# board.net
KiCad netlist of a schematic drawn in EAGLE
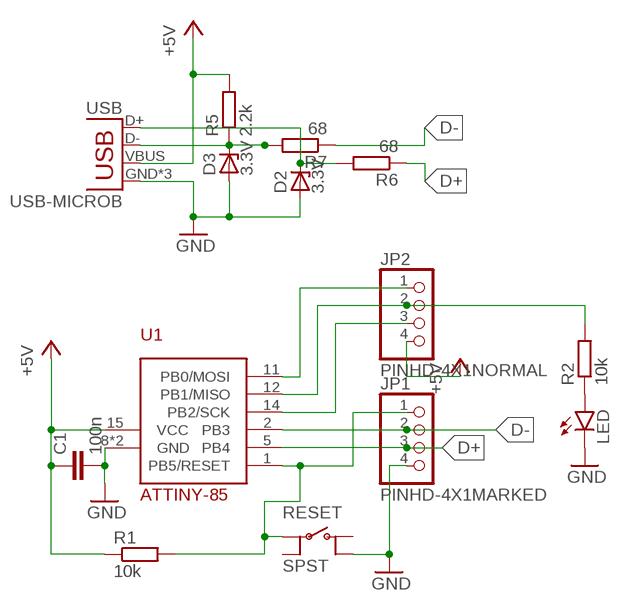
[diagram p0: schematic, sheet 1]

(export (version "E")
  (design (tool "Eeschema 10.0.6"))
  (components
    (comp (ref "C1")
      (value "100n")
      (footprint "eagle-import:C0603")
      (libsource (lib "eagle-import") (part "C-EUC0603"))
    )
    (comp (ref "D2")
      (value "3.3V")
      (footprint "eagle-import:SOD80C")
      (libsource (lib "eagle-import") (part "ZENER-DIODESOD80C"))
    )
    (comp (ref "D3")
      (value "3.3V")
      (footprint "eagle-import:SOD80C")
      (libsource (lib "eagle-import") (part "ZENER-DIODESOD80C"))
    )
    (comp (ref "JP1")
      (value "PINHD-4X1MARKED")
      (footprint "eagle-import:PINHD-1X4-MARKED")
      (libsource (lib "eagle-import") (part "PINHD-4X1MARKED"))
    )
    (comp (ref "JP2")
      (value "PINHD-4X1NORMAL")
      (footprint "eagle-import:PINHD-1X4")
      (libsource (lib "eagle-import") (part "PINHD-4X1NORMAL"))
    )
    (comp (ref "LED")
      (value "LED0603")
      (footprint "eagle-import:LED-0603")
      (libsource (lib "eagle-import") (part "LED0603"))
    )
    (comp (ref "R1")
      (value "10k")
      (footprint "eagle-import:R0402")
      (libsource (lib "eagle-import") (part "R-EU_R0402"))
    )
    (comp (ref "R2")
      (value "10k")
      (footprint "eagle-import:R0402")
      (libsource (lib "eagle-import") (part "R-EU_R0402"))
    )
    (comp (ref "R5")
      (value "2.2k")
      (footprint "eagle-import:R0402")
      (libsource (lib "eagle-import") (part "R-EU_R0402"))
    )
    (comp (ref "R6")
      (value "68")
      (footprint "eagle-import:R0402")
      (libsource (lib "eagle-import") (part "R-EU_R0402"))
    )
    (comp (ref "R7")
      (value "68")
      (footprint "eagle-import:R0402")
      (libsource (lib "eagle-import") (part "R-EU_R0402"))
    )
    (comp (ref "RESET")
      (value "SPST")
      (footprint "eagle-import:WUERTH-SPST-SMD")
      (libsource (lib "eagle-import") (part "SPST"))
    )
    (comp (ref "U1")
      (value "ATTINY-85")
      (footprint "eagle-import:QFN20")
      (libsource (lib "eagle-import") (part "ATTINY-85QFN-EARTHED-CENTER"))
    )
    (comp (ref "USB")
      (value "USB-MICROB")
      (footprint "eagle-import:USB-MICROB")
      (libsource (lib "eagle-import") (part "USB-MICROB"))
    )
  )
  (nets
    (net (code "1") (name "+5V") (class "Default")
      (node (ref "C1") (pin "1") (pinfunction "1_1") (pintype "passive"))
      (node (ref "JP2") (pin "4") (pinfunction "4_4") (pintype "passive"))
      (node (ref "R1") (pin "1") (pinfunction "1_1") (pintype "passive"))
      (node (ref "R5") (pin "2") (pinfunction "2_2") (pintype "passive"))
      (node (ref "U1") (pin "15") (pinfunction "VCC_15") (pintype "power_in"))
      (node (ref "USB") (pin "VBUS") (pinfunction "VBUS_VBUS") (pintype "bidirectional"))
    )
    (net (code "2") (name "D+") (class "Default")
      (node (ref "JP1") (pin "3") (pinfunction "3_3") (pintype "passive"))
      (node (ref "R6") (pin "1") (pinfunction "1_1") (pintype "passive"))
      (node (ref "U1") (pin "5") (pinfunction "PB4_5") (pintype "bidirectional"))
    )
    (net (code "3") (name "D-") (class "Default")
      (node (ref "JP1") (pin "2") (pinfunction "2_2") (pintype "passive"))
      (node (ref "R7") (pin "1") (pinfunction "1_1") (pintype "passive"))
      (node (ref "U1") (pin "2") (pinfunction "PB3_2") (pintype "bidirectional"))
    )
    (net (code "4") (name "GND") (class "Default")
      (node (ref "C1") (pin "2") (pinfunction "2_2") (pintype "passive"))
      (node (ref "D2") (pin "A") (pinfunction "A_A") (pintype "passive"))
      (node (ref "D3") (pin "A") (pinfunction "A_A") (pintype "passive"))
      (node (ref "JP1") (pin "4") (pinfunction "4_4") (pintype "passive"))
      (node (ref "LED") (pin "C") (pinfunction "C_C") (pintype "passive"))
      (node (ref "RESET") (pin "4") (pinfunction "O2_4") (pintype "passive"))
      (node (ref "U1") (pin "8") (pinfunction "GND_8") (pintype "power_in"))
      (node (ref "U1") (pin "EP") (pinfunction "GND_EP") (pintype "power_in"))
      (node (ref "USB") (pin "GND") (pinfunction "GND_GND") (pintype "bidirectional"))
      (node (ref "USB") (pin "MT1") (pinfunction "GND_MT1") (pintype "bidirectional"))
      (node (ref "USB") (pin "MT2") (pinfunction "GND_MT2") (pintype "bidirectional"))
    )
    (net (code "5") (name "Net-(D2-PadC)") (class "Default")
      (node (ref "D2") (pin "C") (pinfunction "C_C") (pintype "passive"))
      (node (ref "R6") (pin "2") (pinfunction "2_2") (pintype "passive"))
      (node (ref "USB") (pin "D+") (pinfunction "D+_D+") (pintype "bidirectional"))
    )
    (net (code "6") (name "Net-(D3-PadC)") (class "Default")
      (node (ref "D3") (pin "C") (pinfunction "C_C") (pintype "passive"))
      (node (ref "R5") (pin "1") (pinfunction "1_1") (pintype "passive"))
      (node (ref "R7") (pin "2") (pinfunction "2_2") (pintype "passive"))
      (node (ref "USB") (pin "D-") (pinfunction "D-_D-") (pintype "bidirectional"))
    )
    (net (code "7") (name "Net-(LED-PadA)") (class "Default")
      (node (ref "LED") (pin "A") (pinfunction "A_A") (pintype "passive"))
      (node (ref "R2") (pin "1") (pinfunction "1_1") (pintype "passive"))
    )
    (net (code "8") (name "Net-(RESET-P)") (class "Default")
      (node (ref "JP1") (pin "1") (pinfunction "1_1") (pintype "passive"))
      (node (ref "R1") (pin "2") (pinfunction "2_2") (pintype "passive"))
      (node (ref "RESET") (pin "1") (pinfunction "P_1") (pintype "passive"))
      (node (ref "U1") (pin "1") (pinfunction "PB5/RESET_1") (pintype "bidirectional"))
    )
    (net (code "9") (name "Net-(U1-PB0{slash}MOSI)") (class "Default")
      (node (ref "JP2") (pin "1") (pinfunction "1_1") (pintype "passive"))
      (node (ref "U1") (pin "11") (pinfunction "PB0/MOSI_11") (pintype "bidirectional"))
    )
    (net (code "10") (name "Net-(U1-PB1{slash}MISO)") (class "Default")
      (node (ref "JP2") (pin "2") (pinfunction "2_2") (pintype "passive"))
      (node (ref "R2") (pin "2") (pinfunction "2_2") (pintype "passive"))
      (node (ref "U1") (pin "12") (pinfunction "PB1/MISO_12") (pintype "bidirectional"))
    )
    (net (code "11") (name "Net-(U1-PB2{slash}SCK)") (class "Default")
      (node (ref "JP2") (pin "3") (pinfunction "3_3") (pintype "passive"))
      (node (ref "U1") (pin "14") (pinfunction "PB2/SCK_14") (pintype "bidirectional"))
    )
    (net (code "12") (name "unconnected-(RESET-O-Pad2)") (class "Default")
      (node (ref "RESET") (pin "2") (pinfunction "O_2") (pintype "passive"))
    )
    (net (code "13") (name "unconnected-(RESET-P2-Pad3)") (class "Default")
      (node (ref "RESET") (pin "3") (pinfunction "P2_3") (pintype "passive"))
    )
  )
)
